# Thermistors.net
KiCad netlist of a schematic drawn in Altium Designer
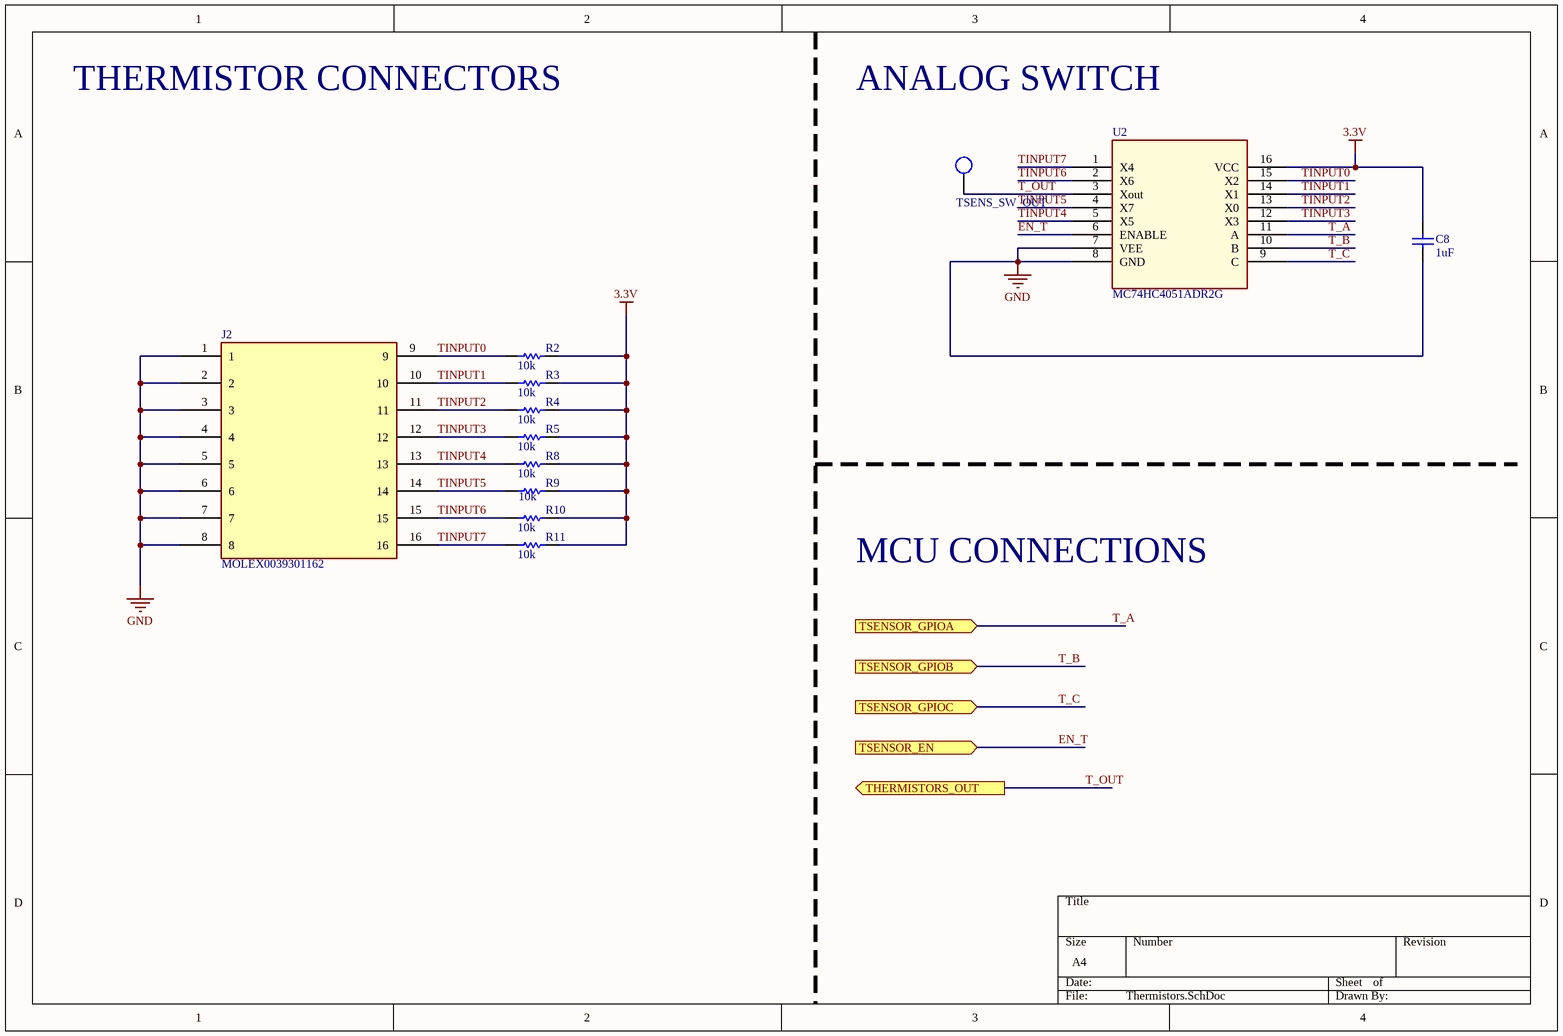
[diagram p0: Thermistors.SchDoc]

(export (version "E")
  (design (tool "Eeschema 10.0.6"))
  (components
    (comp (ref "C8")
      (value "1uF")
      (footprint "0603 - Capacitor")
      (description "Nonpolarized Capacitor")
      (fields (field (name "Comment") "Capacitor - Nonpolarized"))
      (libsource (lib "General") (part "Capacitor - Nonpolarized"))
    )
    (comp (ref "J2")
      (value "MOLEX0039301162")
      (footprint "MOLEX0039301162")
      (description "Connector Header Through Hole, Right Angle 16 position 0.165\" (4.20mm)")
      (fields (field (name "MANUFACTURER") "Molex") (field (name "MANUFACTURER PART NUMBER") "0039301082"))
      (libsource (lib "GeneralConnectors") (part "MOLEX0039301162"))
    )
    (comp (ref "R2")
      (value "10k")
      (footprint "0805 - Resistor")
      (description "Resistor")
      (libsource (lib "General") (part "Resistor"))
    )
    (comp (ref "R3")
      (value "10k")
      (footprint "0805 - Resistor")
      (description "Resistor")
      (libsource (lib "General") (part "Resistor"))
    )
    (comp (ref "R4")
      (value "10k")
      (footprint "0805 - Resistor")
      (description "Resistor")
      (libsource (lib "General") (part "Resistor"))
    )
    (comp (ref "R5")
      (value "10k")
      (footprint "0805 - Resistor")
      (description "Resistor")
      (libsource (lib "General") (part "Resistor"))
    )
    (comp (ref "R8")
      (value "10k")
      (footprint "0805 - Resistor")
      (description "Resistor")
      (libsource (lib "General") (part "Resistor"))
    )
    (comp (ref "R9")
      (value "10k")
      (footprint "0805 - Resistor")
      (description "Resistor")
      (libsource (lib "General") (part "Resistor"))
    )
    (comp (ref "R10")
      (value "10k")
      (footprint "0805 - Resistor")
      (description "Resistor")
      (libsource (lib "General") (part "Resistor"))
    )
    (comp (ref "R11")
      (value "10k")
      (footprint "0805 - Resistor")
      (description "Resistor")
      (libsource (lib "General") (part "Resistor"))
    )
    (comp (ref "TSENS_SW_OUT")
      (value "Test Point")
      (footprint "Test Point - 5002")
      (libsource (lib "General") (part "Test Point"))
    )
    (comp (ref "U2")
      (value "MC74HC4051ADR2G")
      (footprint "MC74HC4051ADR2G")
      (description "1 Circuit IC Switch 8:1 100Ohm 16-SOIC")
      (libsource (lib "Embedded") (part "MC74HC4051ADR2G"))
    )
  )
  (nets
    (net (code "1") (name "/EN_T") (class "Default")
      (node (ref "U2") (pin "6") (pinfunction "ENABLE_6") (pintype "passive"))
    )
    (net (code "2") (name "/TINPUT0") (class "Default")
      (node (ref "J2") (pin "9") (pinfunction "9_9") (pintype "passive"))
      (node (ref "R2") (pin "2") (pinfunction "2_2") (pintype "passive"))
      (node (ref "U2") (pin "15") (pinfunction "X2_15") (pintype "passive"))
    )
    (net (code "3") (name "/TINPUT1") (class "Default")
      (node (ref "J2") (pin "10") (pinfunction "10_10") (pintype "passive"))
      (node (ref "R3") (pin "2") (pinfunction "2_2") (pintype "passive"))
      (node (ref "U2") (pin "14") (pinfunction "X1_14") (pintype "passive"))
    )
    (net (code "4") (name "/TINPUT2") (class "Default")
      (node (ref "J2") (pin "11") (pinfunction "11_11") (pintype "passive"))
      (node (ref "R4") (pin "2") (pinfunction "2_2") (pintype "passive"))
      (node (ref "U2") (pin "13") (pinfunction "X0_13") (pintype "passive"))
    )
    (net (code "5") (name "/TINPUT3") (class "Default")
      (node (ref "J2") (pin "12") (pinfunction "12_12") (pintype "passive"))
      (node (ref "R5") (pin "2") (pinfunction "2_2") (pintype "passive"))
      (node (ref "U2") (pin "12") (pinfunction "X3_12") (pintype "passive"))
    )
    (net (code "6") (name "/TINPUT4") (class "Default")
      (node (ref "J2") (pin "13") (pinfunction "13_13") (pintype "passive"))
      (node (ref "R8") (pin "2") (pinfunction "2_2") (pintype "passive"))
      (node (ref "U2") (pin "5") (pinfunction "X5_5") (pintype "passive"))
    )
    (net (code "7") (name "/TINPUT5") (class "Default")
      (node (ref "J2") (pin "14") (pinfunction "14_14") (pintype "passive"))
      (node (ref "R9") (pin "2") (pinfunction "2_2") (pintype "passive"))
      (node (ref "U2") (pin "4") (pinfunction "X7_4") (pintype "passive"))
    )
    (net (code "8") (name "/TINPUT6") (class "Default")
      (node (ref "J2") (pin "15") (pinfunction "15_15") (pintype "passive"))
      (node (ref "R10") (pin "2") (pinfunction "2_2") (pintype "passive"))
      (node (ref "U2") (pin "2") (pinfunction "X6_2") (pintype "passive"))
    )
    (net (code "9") (name "/TINPUT7") (class "Default")
      (node (ref "J2") (pin "16") (pinfunction "16_16") (pintype "passive"))
      (node (ref "R11") (pin "2") (pinfunction "2_2") (pintype "passive"))
      (node (ref "U2") (pin "1") (pinfunction "X4_1") (pintype "passive"))
    )
    (net (code "10") (name "/T_A") (class "Default")
      (node (ref "U2") (pin "11") (pinfunction "A_11") (pintype "passive"))
    )
    (net (code "11") (name "/T_B") (class "Default")
      (node (ref "U2") (pin "10") (pinfunction "B_10") (pintype "passive"))
    )
    (net (code "12") (name "/T_C") (class "Default")
      (node (ref "U2") (pin "9") (pinfunction "C_9") (pintype "passive"))
    )
    (net (code "13") (name "/T_OUT") (class "Default")
      (node (ref "TSENS_SW_OUT") (pin "1") (pinfunction "0_1") (pintype "passive"))
      (node (ref "U2") (pin "3") (pinfunction "Xout_3") (pintype "passive"))
    )
    (net (code "14") (name "3.3V") (class "Default")
      (node (ref "C8") (pin "2") (pinfunction "2_2") (pintype "passive"))
      (node (ref "R10") (pin "1") (pinfunction "1_1") (pintype "passive"))
      (node (ref "R11") (pin "1") (pinfunction "1_1") (pintype "passive"))
      (node (ref "R2") (pin "1") (pinfunction "1_1") (pintype "passive"))
      (node (ref "R3") (pin "1") (pinfunction "1_1") (pintype "passive"))
      (node (ref "R4") (pin "1") (pinfunction "1_1") (pintype "passive"))
      (node (ref "R5") (pin "1") (pinfunction "1_1") (pintype "passive"))
      (node (ref "R8") (pin "1") (pinfunction "1_1") (pintype "passive"))
      (node (ref "R9") (pin "1") (pinfunction "1_1") (pintype "passive"))
      (node (ref "U2") (pin "16") (pinfunction "VCC_16") (pintype "power_in"))
    )
    (net (code "15") (name "GND") (class "Default")
      (node (ref "C8") (pin "1") (pinfunction "1_1") (pintype "passive"))
      (node (ref "J2") (pin "1") (pinfunction "1_1") (pintype "passive"))
      (node (ref "J2") (pin "2") (pinfunction "2_2") (pintype "passive"))
      (node (ref "J2") (pin "3") (pinfunction "3_3") (pintype "passive"))
      (node (ref "J2") (pin "4") (pinfunction "4_4") (pintype "passive"))
      (node (ref "J2") (pin "5") (pinfunction "5_5") (pintype "passive"))
      (node (ref "J2") (pin "6") (pinfunction "6_6") (pintype "passive"))
      (node (ref "J2") (pin "7") (pinfunction "7_7") (pintype "passive"))
      (node (ref "J2") (pin "8") (pinfunction "8_8") (pintype "passive"))
      (node (ref "U2") (pin "7") (pinfunction "VEE_7") (pintype "power_in"))
      (node (ref "U2") (pin "8") (pinfunction "GND_8") (pintype "power_in"))
    )
  )
)
